# test_schematic.net
KiCad netlist of a schematic drawn in EAGLE
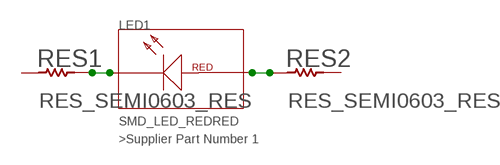
[diagram p0: schematic, sheet 1]

(export (version "E")
  (design (tool "Eeschema 10.0.6"))
  (components
    (comp (ref "LED1")
      (value "SMD_LED_REDRED")
      (footprint "eagle-import:0603_LED_RED")
      (fields (field (name "MANUFACTURER_PART_NUMBER") "150060RS75000"))
      (libsource (lib "eagle-import") (part "SMD_LED_REDRED"))
    )
    (comp (ref "RES1")
      (value "RES_SEMI0603_RES")
      (footprint "eagle-import:0603_RESISTOR")
      (fields (field (name "MANUFACTURER_PART_NUMBER") "311-619KHRCT-ND"))
      (libsource (lib "eagle-import") (part "RES_SEMI0603_RES"))
    )
    (comp (ref "RES2")
      (value "RES_SEMI0603_RES")
      (footprint "eagle-import:0603_RESISTOR")
      (fields (field (name "MANUFACTURER_PART_NUMBER") "311-619KHRCT-ND"))
      (libsource (lib "eagle-import") (part "RES_SEMI0603_RES"))
    )
  )
  (nets
    (net (code "1") (name "Net-(LED1-A)") (class "Default")
      (node (ref "LED1") (pin "2") (pinfunction "A_2") (pintype "passive"))
      (node (ref "RES2") (pin "1") (pinfunction "1_1") (pintype "passive"))
    )
    (net (code "2") (name "Net-(LED1-K)") (class "Default")
      (node (ref "LED1") (pin "1") (pinfunction "K_1") (pintype "passive"))
      (node (ref "RES1") (pin "2") (pinfunction "2_2") (pintype "passive"))
    )
    (net (code "3") (name "unconnected-(RES1-Pad1)") (class "Default")
      (node (ref "RES1") (pin "1") (pinfunction "1_1") (pintype "passive"))
    )
    (net (code "4") (name "unconnected-(RES2-Pad2)") (class "Default")
      (node (ref "RES2") (pin "2") (pinfunction "2_2") (pintype "passive"))
    )
  )
)
